# MDAS_Controller_V1.net
KiCad netlist of a schematic drawn in EAGLE
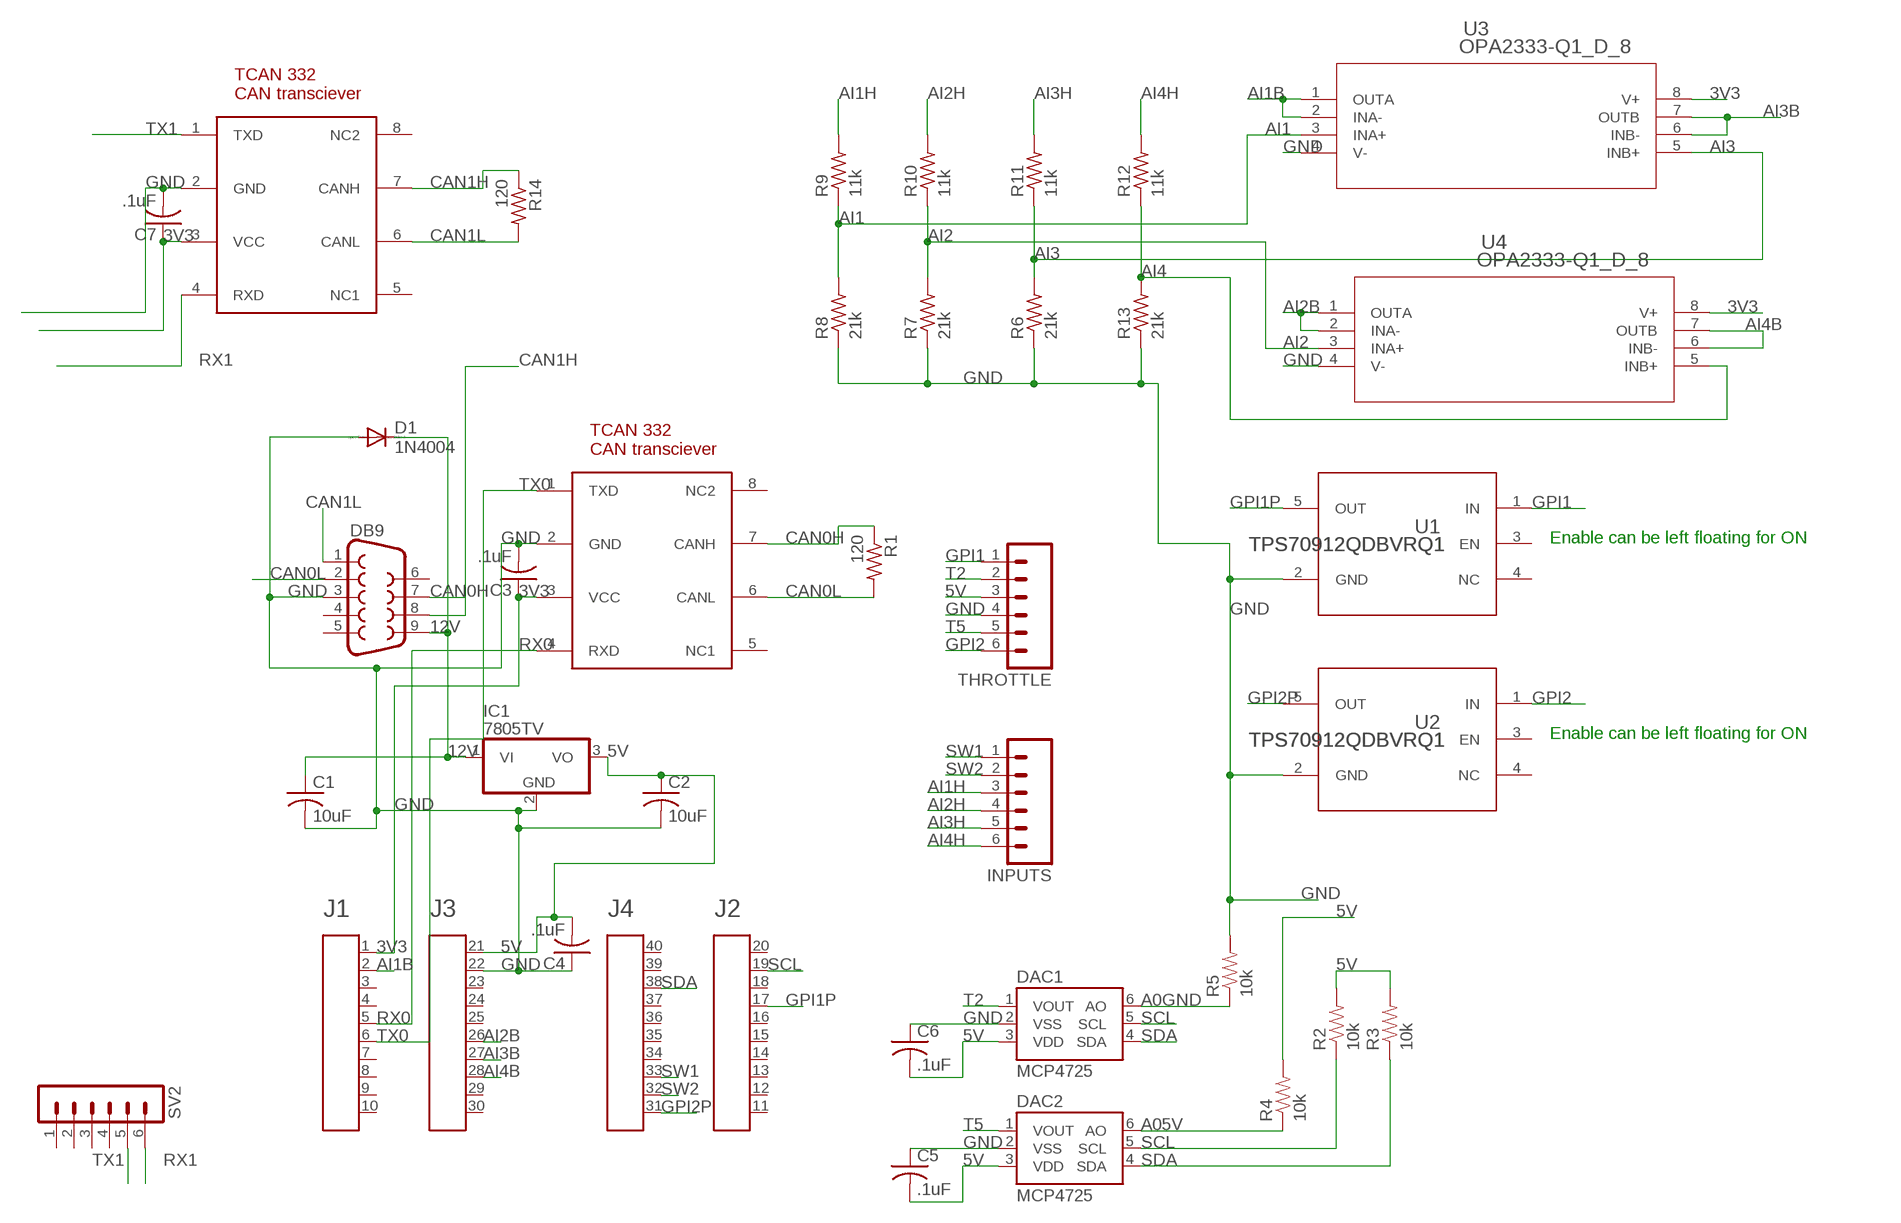
[diagram p0: schematic, sheet 1]

(export (version "E")
  (design (tool "Eeschema 10.0.6"))
  (components
    (comp (ref "A1")
      (value "HEADER4X10-BOOSTERPACK")
      (footprint "eagle-import:4X10-BOOSTERPACK")
      (libsource (lib "eagle-import") (part "HEADER4X10-BOOSTERPACK"))
    )
    (comp (ref "C1")
      (value "10uF")
      (footprint "eagle-import:C1206K")
      (libsource (lib "eagle-import") (part "C-USC1206K"))
    )
    (comp (ref "C2")
      (value "10uF")
      (footprint "eagle-import:C1206K")
      (libsource (lib "eagle-import") (part "C-USC1206K"))
    )
    (comp (ref "C3")
      (value ".1uF")
      (footprint "eagle-import:C0603")
      (libsource (lib "eagle-import") (part "adafruit_420_C-USC0603"))
    )
    (comp (ref "C4")
      (value ".1uF")
      (footprint "eagle-import:C0603")
      (libsource (lib "eagle-import") (part "adafruit_420_C-USC0603"))
    )
    (comp (ref "C5")
      (value ".1uF")
      (footprint "eagle-import:C0603")
      (libsource (lib "eagle-import") (part "adafruit_420_C-USC0603"))
    )
    (comp (ref "C6")
      (value ".1uF")
      (footprint "eagle-import:C0603")
      (libsource (lib "eagle-import") (part "adafruit_420_C-USC0603"))
    )
    (comp (ref "C7")
      (value ".1uF")
      (footprint "eagle-import:C0603")
      (libsource (lib "eagle-import") (part "adafruit_420_C-USC0603"))
    )
    (comp (ref "CAN_TRANSCIEVER")
      (value "TCAN332")
      (footprint "eagle-import:SOIC127P600X172-8N")
      (libsource (lib "eagle-import") (part "TCAN332"))
    )
    (comp (ref "CAN_TRANSCIEVER1")
      (value "TCAN332")
      (footprint "eagle-import:SOIC127P600X172-8N")
      (libsource (lib "eagle-import") (part "TCAN332"))
    )
    (comp (ref "D1")
      (value "1N4004")
      (footprint "eagle-import:DO41-10")
      (libsource (lib "eagle-import") (part "1N4004"))
    )
    (comp (ref "DAC1")
      (value "MCP4725")
      (footprint "eagle-import:SOT23-6")
      (libsource (lib "eagle-import") (part "MCP4725SOT-23"))
    )
    (comp (ref "DAC2")
      (value "MCP4725")
      (footprint "eagle-import:SOT23-6")
      (libsource (lib "eagle-import") (part "MCP4725SOT-23"))
    )
    (comp (ref "DB9")
      (value "DB9FEMALE")
      (footprint "eagle-import:DB9")
      (libsource (lib "eagle-import") (part "DB9FEMALE"))
    )
    (comp (ref "IC1")
      (value "7805TV")
      (footprint "eagle-import:TO220V")
      (libsource (lib "eagle-import") (part "78TV05"))
    )
    (comp (ref "INPUTS")
      (value "M06SMD-1MM")
      (footprint "eagle-import:1X06-1MM")
      (libsource (lib "eagle-import") (part "M06SMD-1MM"))
    )
    (comp (ref "R1")
      (value "120")
      (footprint "eagle-import:0207_10")
      (libsource (lib "eagle-import") (part "adafruit_420_R-US_0207/10"))
    )
    (comp (ref "R2")
      (value "10k")
      (footprint "eagle-import:0603-RES")
      (libsource (lib "eagle-import") (part "RESISTOR0603-RES"))
    )
    (comp (ref "R3")
      (value "10k")
      (footprint "eagle-import:0603-RES")
      (libsource (lib "eagle-import") (part "RESISTOR0603-RES"))
    )
    (comp (ref "R4")
      (value "10k")
      (footprint "eagle-import:0603-RES")
      (libsource (lib "eagle-import") (part "RESISTOR0603-RES"))
    )
    (comp (ref "R5")
      (value "10k")
      (footprint "eagle-import:0603-RES")
      (libsource (lib "eagle-import") (part "RESISTOR0603-RES"))
    )
    (comp (ref "R6")
      (value "21k")
      (footprint "eagle-import:R0603")
      (libsource (lib "eagle-import") (part "R-US_R0603"))
    )
    (comp (ref "R7")
      (value "21k")
      (footprint "eagle-import:R0603")
      (libsource (lib "eagle-import") (part "R-US_R0603"))
    )
    (comp (ref "R8")
      (value "21k")
      (footprint "eagle-import:R0603")
      (libsource (lib "eagle-import") (part "R-US_R0603"))
    )
    (comp (ref "R9")
      (value "11k")
      (footprint "eagle-import:R0603")
      (libsource (lib "eagle-import") (part "R-US_R0603"))
    )
    (comp (ref "R10")
      (value "11k")
      (footprint "eagle-import:R0603")
      (libsource (lib "eagle-import") (part "R-US_R0603"))
    )
    (comp (ref "R11")
      (value "11k")
      (footprint "eagle-import:R0603")
      (libsource (lib "eagle-import") (part "R-US_R0603"))
    )
    (comp (ref "R12")
      (value "11k")
      (footprint "eagle-import:R0603")
      (libsource (lib "eagle-import") (part "R-US_R0603"))
    )
    (comp (ref "R13")
      (value "21k")
      (footprint "eagle-import:R0603")
      (libsource (lib "eagle-import") (part "R-US_R0603"))
    )
    (comp (ref "R14")
      (value "120")
      (footprint "eagle-import:0207_10")
      (libsource (lib "eagle-import") (part "adafruit_420_R-US_0207/10"))
    )
    (comp (ref "SV2")
      (value "MA06-1")
      (footprint "eagle-import:MA06-1")
      (libsource (lib "eagle-import") (part "MA06-1"))
    )
    (comp (ref "THROTTLE")
      (value "M06SMD-1MM")
      (footprint "eagle-import:1X06-1MM")
      (libsource (lib "eagle-import") (part "M06SMD-1MM"))
    )
    (comp (ref "U1")
      (value "TPS70912QDBVRQ1")
      (footprint "eagle-import:DBV0005A_N")
      (libsource (lib "eagle-import") (part "TPS70912QDBVRQ1"))
    )
    (comp (ref "U2")
      (value "TPS70912QDBVRQ1")
      (footprint "eagle-import:DBV0005A_N")
      (libsource (lib "eagle-import") (part "TPS70912QDBVRQ1"))
    )
    (comp (ref "U3")
      (value "OPA2333-Q1_D_8")
      (footprint "eagle-import:D8")
      (fields (field (name "MANUFACTURER_PART_NUMBER") "opa2333q1_d_8"))
      (libsource (lib "eagle-import") (part "OPA2333-Q1_D_8"))
    )
    (comp (ref "U4")
      (value "OPA2333-Q1_D_8")
      (footprint "eagle-import:D8")
      (fields (field (name "MANUFACTURER_PART_NUMBER") "opa2333q1_d_8"))
      (libsource (lib "eagle-import") (part "OPA2333-Q1_D_8"))
    )
  )
  (nets
    (net (code "1") (name "/3V3") (class "Default")
      (node (ref "A1") (pin "1") (pinfunction "P$1_1") (pintype "bidirectional"))
      (node (ref "C3") (pin "1") (pinfunction "1_1") (pintype "passive"))
      (node (ref "C7") (pin "1") (pinfunction "1_1") (pintype "passive"))
      (node (ref "CAN_TRANSCIEVER") (pin "3") (pinfunction "VCC_3") (pintype "bidirectional"))
      (node (ref "CAN_TRANSCIEVER1") (pin "3") (pinfunction "VCC_3") (pintype "bidirectional"))
      (node (ref "U3") (pin "8") (pinfunction "V+_8") (pintype "power_in"))
      (node (ref "U4") (pin "8") (pinfunction "V+_8") (pintype "power_in"))
    )
    (net (code "2") (name "/5V") (class "Default")
      (node (ref "A1") (pin "21") (pinfunction "P$21_21") (pintype "bidirectional"))
      (node (ref "C2") (pin "1") (pinfunction "1_1") (pintype "passive"))
      (node (ref "C4") (pin "2") (pinfunction "2_2") (pintype "passive"))
      (node (ref "C5") (pin "2") (pinfunction "2_2") (pintype "passive"))
      (node (ref "C6") (pin "2") (pinfunction "2_2") (pintype "passive"))
      (node (ref "DAC1") (pin "3") (pinfunction "VDD_3") (pintype "bidirectional"))
      (node (ref "DAC2") (pin "3") (pinfunction "VDD_3") (pintype "bidirectional"))
      (node (ref "IC1") (pin "3") (pinfunction "VO_3") (pintype "passive"))
      (node (ref "R2") (pin "2") (pinfunction "2_2") (pintype "passive"))
      (node (ref "R3") (pin "2") (pinfunction "2_2") (pintype "passive"))
      (node (ref "R4") (pin "2") (pinfunction "2_2") (pintype "passive"))
      (node (ref "THROTTLE") (pin "3") (pinfunction "3_3") (pintype "passive"))
    )
    (net (code "3") (name "/12V") (class "Default")
      (node (ref "C1") (pin "1") (pinfunction "1_1") (pintype "passive"))
      (node (ref "D1") (pin "C") (pinfunction "C_C") (pintype "passive"))
      (node (ref "DB9") (pin "9") (pinfunction "9_9") (pintype "passive"))
      (node (ref "IC1") (pin "1") (pinfunction "VI_1") (pintype "input"))
    )
    (net (code "4") (name "/A0GND") (class "Default")
      (node (ref "DAC1") (pin "6") (pinfunction "AO_6") (pintype "bidirectional"))
      (node (ref "R5") (pin "1") (pinfunction "1_1") (pintype "passive"))
    )
    (net (code "5") (name "/A05V") (class "Default")
      (node (ref "DAC2") (pin "6") (pinfunction "AO_6") (pintype "bidirectional"))
      (node (ref "R4") (pin "1") (pinfunction "1_1") (pintype "passive"))
    )
    (net (code "6") (name "/AI1") (class "Default")
      (node (ref "R8") (pin "2") (pinfunction "2_2") (pintype "passive"))
      (node (ref "R9") (pin "1") (pinfunction "1_1") (pintype "passive"))
      (node (ref "U3") (pin "3") (pinfunction "INA+_3") (pintype "input"))
    )
    (net (code "7") (name "/AI1B") (class "Default")
      (node (ref "A1") (pin "2") (pinfunction "P$2_2") (pintype "bidirectional"))
      (node (ref "U3") (pin "1") (pinfunction "OUTA_1") (pintype "output"))
      (node (ref "U3") (pin "2") (pinfunction "INA-_2") (pintype "input"))
    )
    (net (code "8") (name "/AI1H") (class "Default")
      (node (ref "INPUTS") (pin "3") (pinfunction "3_3") (pintype "passive"))
      (node (ref "R9") (pin "2") (pinfunction "2_2") (pintype "passive"))
    )
    (net (code "9") (name "/AI2") (class "Default")
      (node (ref "R10") (pin "1") (pinfunction "1_1") (pintype "passive"))
      (node (ref "R7") (pin "2") (pinfunction "2_2") (pintype "passive"))
      (node (ref "U4") (pin "3") (pinfunction "INA+_3") (pintype "input"))
    )
    (net (code "10") (name "/AI2B") (class "Default")
      (node (ref "A1") (pin "26") (pinfunction "P$26_26") (pintype "bidirectional"))
      (node (ref "U4") (pin "1") (pinfunction "OUTA_1") (pintype "output"))
      (node (ref "U4") (pin "2") (pinfunction "INA-_2") (pintype "input"))
    )
    (net (code "11") (name "/AI2H") (class "Default")
      (node (ref "INPUTS") (pin "4") (pinfunction "4_4") (pintype "passive"))
      (node (ref "R10") (pin "2") (pinfunction "2_2") (pintype "passive"))
    )
    (net (code "12") (name "/AI3") (class "Default")
      (node (ref "R11") (pin "1") (pinfunction "1_1") (pintype "passive"))
      (node (ref "R6") (pin "2") (pinfunction "2_2") (pintype "passive"))
      (node (ref "U3") (pin "5") (pinfunction "INB+_5") (pintype "input"))
    )
    (net (code "13") (name "/AI3B") (class "Default")
      (node (ref "A1") (pin "27") (pinfunction "P$27_27") (pintype "bidirectional"))
      (node (ref "U3") (pin "6") (pinfunction "INB-_6") (pintype "input"))
      (node (ref "U3") (pin "7") (pinfunction "OUTB_7") (pintype "output"))
    )
    (net (code "14") (name "/AI3H") (class "Default")
      (node (ref "INPUTS") (pin "5") (pinfunction "5_5") (pintype "passive"))
      (node (ref "R11") (pin "2") (pinfunction "2_2") (pintype "passive"))
    )
    (net (code "15") (name "/AI4") (class "Default")
      (node (ref "R12") (pin "1") (pinfunction "1_1") (pintype "passive"))
      (node (ref "R13") (pin "2") (pinfunction "2_2") (pintype "passive"))
      (node (ref "U4") (pin "5") (pinfunction "INB+_5") (pintype "input"))
    )
    (net (code "16") (name "/AI4B") (class "Default")
      (node (ref "A1") (pin "28") (pinfunction "P$28_28") (pintype "bidirectional"))
      (node (ref "U4") (pin "6") (pinfunction "INB-_6") (pintype "input"))
      (node (ref "U4") (pin "7") (pinfunction "OUTB_7") (pintype "output"))
    )
    (net (code "17") (name "/AI4H") (class "Default")
      (node (ref "INPUTS") (pin "6") (pinfunction "6_6") (pintype "passive"))
      (node (ref "R12") (pin "2") (pinfunction "2_2") (pintype "passive"))
    )
    (net (code "18") (name "/CAN0H") (class "Default")
      (node (ref "CAN_TRANSCIEVER") (pin "7") (pinfunction "CANH_7") (pintype "bidirectional"))
      (node (ref "DB9") (pin "7") (pinfunction "7_7") (pintype "passive"))
      (node (ref "R1") (pin "1") (pinfunction "1_1") (pintype "passive"))
    )
    (net (code "19") (name "/CAN0L") (class "Default")
      (node (ref "CAN_TRANSCIEVER") (pin "6") (pinfunction "CANL_6") (pintype "bidirectional"))
      (node (ref "DB9") (pin "2") (pinfunction "2_2") (pintype "passive"))
      (node (ref "R1") (pin "2") (pinfunction "2_2") (pintype "passive"))
    )
    (net (code "20") (name "/CAN1H") (class "Default")
      (node (ref "CAN_TRANSCIEVER1") (pin "7") (pinfunction "CANH_7") (pintype "bidirectional"))
      (node (ref "DB9") (pin "8") (pinfunction "8_8") (pintype "passive"))
      (node (ref "R14") (pin "1") (pinfunction "1_1") (pintype "passive"))
    )
    (net (code "21") (name "/CAN1L") (class "Default")
      (node (ref "CAN_TRANSCIEVER1") (pin "6") (pinfunction "CANL_6") (pintype "bidirectional"))
      (node (ref "DB9") (pin "1") (pinfunction "1_1") (pintype "passive"))
      (node (ref "R14") (pin "2") (pinfunction "2_2") (pintype "passive"))
    )
    (net (code "22") (name "/GND") (class "Default")
      (node (ref "A1") (pin "22") (pinfunction "P$22_22") (pintype "bidirectional"))
      (node (ref "C1") (pin "2") (pinfunction "2_2") (pintype "passive"))
      (node (ref "C2") (pin "2") (pinfunction "2_2") (pintype "passive"))
      (node (ref "C3") (pin "2") (pinfunction "2_2") (pintype "passive"))
      (node (ref "C4") (pin "1") (pinfunction "1_1") (pintype "passive"))
      (node (ref "C5") (pin "1") (pinfunction "1_1") (pintype "passive"))
      (node (ref "C6") (pin "1") (pinfunction "1_1") (pintype "passive"))
      (node (ref "C7") (pin "2") (pinfunction "2_2") (pintype "passive"))
      (node (ref "CAN_TRANSCIEVER") (pin "2") (pinfunction "GND_2") (pintype "bidirectional"))
      (node (ref "CAN_TRANSCIEVER1") (pin "2") (pinfunction "GND_2") (pintype "bidirectional"))
      (node (ref "D1") (pin "A") (pinfunction "A_A") (pintype "passive"))
      (node (ref "DAC1") (pin "2") (pinfunction "VSS_2") (pintype "bidirectional"))
      (node (ref "DAC2") (pin "2") (pinfunction "VSS_2") (pintype "bidirectional"))
      (node (ref "DB9") (pin "3") (pinfunction "3_3") (pintype "passive"))
      (node (ref "IC1") (pin "2") (pinfunction "GND_2") (pintype "passive"))
      (node (ref "R13") (pin "1") (pinfunction "1_1") (pintype "passive"))
      (node (ref "R5") (pin "2") (pinfunction "2_2") (pintype "passive"))
      (node (ref "R6") (pin "1") (pinfunction "1_1") (pintype "passive"))
      (node (ref "R7") (pin "1") (pinfunction "1_1") (pintype "passive"))
      (node (ref "R8") (pin "1") (pinfunction "1_1") (pintype "passive"))
      (node (ref "THROTTLE") (pin "4") (pinfunction "4_4") (pintype "passive"))
      (node (ref "U1") (pin "2") (pinfunction "GND_2") (pintype "power_in"))
      (node (ref "U2") (pin "2") (pinfunction "GND_2") (pintype "power_in"))
      (node (ref "U3") (pin "4") (pinfunction "V-_4") (pintype "power_in"))
      (node (ref "U4") (pin "4") (pinfunction "V-_4") (pintype "power_in"))
    )
    (net (code "23") (name "/GPI1") (class "Default")
      (node (ref "THROTTLE") (pin "1") (pinfunction "1_1") (pintype "passive"))
      (node (ref "U1") (pin "1") (pinfunction "IN_1") (pintype "power_in"))
    )
    (net (code "24") (name "/GPI1P") (class "Default")
      (node (ref "A1") (pin "17") (pinfunction "P$17_17") (pintype "bidirectional"))
      (node (ref "U1") (pin "5") (pinfunction "OUT_5") (pintype "power_in"))
    )
    (net (code "25") (name "/GPI2") (class "Default")
      (node (ref "THROTTLE") (pin "6") (pinfunction "6_6") (pintype "passive"))
      (node (ref "U2") (pin "1") (pinfunction "IN_1") (pintype "power_in"))
    )
    (net (code "26") (name "/GPI2P") (class "Default")
      (node (ref "A1") (pin "31") (pinfunction "P$31_31") (pintype "bidirectional"))
      (node (ref "U2") (pin "5") (pinfunction "OUT_5") (pintype "power_in"))
    )
    (net (code "27") (name "/RX0") (class "Default")
      (node (ref "A1") (pin "5") (pinfunction "P$5_5") (pintype "bidirectional"))
      (node (ref "CAN_TRANSCIEVER") (pin "4") (pinfunction "RXD_4") (pintype "bidirectional"))
    )
    (net (code "28") (name "/RX1") (class "Default")
      (node (ref "CAN_TRANSCIEVER1") (pin "4") (pinfunction "RXD_4") (pintype "bidirectional"))
      (node (ref "SV2") (pin "6") (pinfunction "6_6") (pintype "passive"))
    )
    (net (code "29") (name "/SCL") (class "Default")
      (node (ref "A1") (pin "19") (pinfunction "P$19_19") (pintype "bidirectional"))
      (node (ref "DAC1") (pin "5") (pinfunction "SCL_5") (pintype "bidirectional"))
      (node (ref "DAC2") (pin "5") (pinfunction "SCL_5") (pintype "bidirectional"))
      (node (ref "R2") (pin "1") (pinfunction "1_1") (pintype "passive"))
    )
    (net (code "30") (name "/SDA") (class "Default")
      (node (ref "A1") (pin "38") (pinfunction "P$38_38") (pintype "bidirectional"))
      (node (ref "DAC1") (pin "4") (pinfunction "SDA_4") (pintype "bidirectional"))
      (node (ref "DAC2") (pin "4") (pinfunction "SDA_4") (pintype "bidirectional"))
      (node (ref "R3") (pin "1") (pinfunction "1_1") (pintype "passive"))
    )
    (net (code "31") (name "/SW1") (class "Default")
      (node (ref "A1") (pin "33") (pinfunction "P$33_33") (pintype "bidirectional"))
      (node (ref "INPUTS") (pin "1") (pinfunction "1_1") (pintype "passive"))
    )
    (net (code "32") (name "/SW2") (class "Default")
      (node (ref "A1") (pin "32") (pinfunction "P$32_32") (pintype "bidirectional"))
      (node (ref "INPUTS") (pin "2") (pinfunction "2_2") (pintype "passive"))
    )
    (net (code "33") (name "/T2") (class "Default")
      (node (ref "DAC1") (pin "1") (pinfunction "VOUT_1") (pintype "bidirectional"))
      (node (ref "THROTTLE") (pin "2") (pinfunction "2_2") (pintype "passive"))
    )
    (net (code "34") (name "/T5") (class "Default")
      (node (ref "DAC2") (pin "1") (pinfunction "VOUT_1") (pintype "bidirectional"))
      (node (ref "THROTTLE") (pin "5") (pinfunction "5_5") (pintype "passive"))
    )
    (net (code "35") (name "/TX0") (class "Default")
      (node (ref "A1") (pin "6") (pinfunction "P$6_6") (pintype "bidirectional"))
      (node (ref "CAN_TRANSCIEVER") (pin "1") (pinfunction "TXD_1") (pintype "bidirectional"))
    )
    (net (code "36") (name "/TX1") (class "Default")
      (node (ref "CAN_TRANSCIEVER1") (pin "1") (pinfunction "TXD_1") (pintype "bidirectional"))
      (node (ref "SV2") (pin "5") (pinfunction "5_5") (pintype "passive"))
    )
    (net (code "37") (name "unconnected-(A1-P$3-Pad3)") (class "Default")
      (node (ref "A1") (pin "3") (pinfunction "P$3_3") (pintype "bidirectional"))
    )
    (net (code "38") (name "unconnected-(A1-P$4-Pad4)") (class "Default")
      (node (ref "A1") (pin "4") (pinfunction "P$4_4") (pintype "bidirectional"))
    )
    (net (code "39") (name "unconnected-(A1-P$7-Pad7)") (class "Default")
      (node (ref "A1") (pin "7") (pinfunction "P$7_7") (pintype "bidirectional"))
    )
    (net (code "40") (name "unconnected-(A1-P$8-Pad8)") (class "Default")
      (node (ref "A1") (pin "8") (pinfunction "P$8_8") (pintype "bidirectional"))
    )
    (net (code "41") (name "unconnected-(A1-P$9-Pad9)") (class "Default")
      (node (ref "A1") (pin "9") (pinfunction "P$9_9") (pintype "bidirectional"))
    )
    (net (code "42") (name "unconnected-(A1-P$10-Pad10)") (class "Default")
      (node (ref "A1") (pin "10") (pinfunction "P$10_10") (pintype "bidirectional"))
    )
    (net (code "43") (name "unconnected-(A1-P$11-Pad11)") (class "Default")
      (node (ref "A1") (pin "11") (pinfunction "P$11_11") (pintype "bidirectional"))
    )
    (net (code "44") (name "unconnected-(A1-P$12-Pad12)") (class "Default")
      (node (ref "A1") (pin "12") (pinfunction "P$12_12") (pintype "bidirectional"))
    )
    (net (code "45") (name "unconnected-(A1-P$13-Pad13)") (class "Default")
      (node (ref "A1") (pin "13") (pinfunction "P$13_13") (pintype "bidirectional"))
    )
    (net (code "46") (name "unconnected-(A1-P$14-Pad14)") (class "Default")
      (node (ref "A1") (pin "14") (pinfunction "P$14_14") (pintype "bidirectional"))
    )
    (net (code "47") (name "unconnected-(A1-P$15-Pad15)") (class "Default")
      (node (ref "A1") (pin "15") (pinfunction "P$15_15") (pintype "bidirectional"))
    )
    (net (code "48") (name "unconnected-(A1-P$16-Pad16)") (class "Default")
      (node (ref "A1") (pin "16") (pinfunction "P$16_16") (pintype "bidirectional"))
    )
    (net (code "49") (name "unconnected-(A1-P$18-Pad18)") (class "Default")
      (node (ref "A1") (pin "18") (pinfunction "P$18_18") (pintype "bidirectional"))
    )
    (net (code "50") (name "unconnected-(A1-P$20-Pad20)") (class "Default")
      (node (ref "A1") (pin "20") (pinfunction "P$20_20") (pintype "bidirectional"))
    )
    (net (code "51") (name "unconnected-(A1-P$23-Pad23)") (class "Default")
      (node (ref "A1") (pin "23") (pinfunction "P$23_23") (pintype "bidirectional"))
    )
    (net (code "52") (name "unconnected-(A1-P$24-Pad24)") (class "Default")
      (node (ref "A1") (pin "24") (pinfunction "P$24_24") (pintype "bidirectional"))
    )
    (net (code "53") (name "unconnected-(A1-P$25-Pad25)") (class "Default")
      (node (ref "A1") (pin "25") (pinfunction "P$25_25") (pintype "bidirectional"))
    )
    (net (code "54") (name "unconnected-(A1-P$29-Pad29)") (class "Default")
      (node (ref "A1") (pin "29") (pinfunction "P$29_29") (pintype "bidirectional"))
    )
    (net (code "55") (name "unconnected-(A1-P$30-Pad30)") (class "Default")
      (node (ref "A1") (pin "30") (pinfunction "P$30_30") (pintype "bidirectional"))
    )
    (net (code "56") (name "unconnected-(A1-P$34-Pad34)") (class "Default")
      (node (ref "A1") (pin "34") (pinfunction "P$34_34") (pintype "bidirectional"))
    )
    (net (code "57") (name "unconnected-(A1-P$35-Pad35)") (class "Default")
      (node (ref "A1") (pin "35") (pinfunction "P$35_35") (pintype "bidirectional"))
    )
    (net (code "58") (name "unconnected-(A1-P$36-Pad36)") (class "Default")
      (node (ref "A1") (pin "36") (pinfunction "P$36_36") (pintype "bidirectional"))
    )
    (net (code "59") (name "unconnected-(A1-P$37-Pad37)") (class "Default")
      (node (ref "A1") (pin "37") (pinfunction "P$37_37") (pintype "bidirectional"))
    )
    (net (code "60") (name "unconnected-(A1-P$39-Pad39)") (class "Default")
      (node (ref "A1") (pin "39") (pinfunction "P$39_39") (pintype "bidirectional"))
    )
    (net (code "61") (name "unconnected-(A1-P$40-Pad40)") (class "Default")
      (node (ref "A1") (pin "40") (pinfunction "P$40_40") (pintype "bidirectional"))
    )
    (net (code "62") (name "unconnected-(CAN_TRANSCIEVER-NC1-Pad5)") (class "Default")
      (node (ref "CAN_TRANSCIEVER") (pin "5") (pinfunction "NC1_5") (pintype "bidirectional"))
    )
    (net (code "63") (name "unconnected-(CAN_TRANSCIEVER-NC2-Pad8)") (class "Default")
      (node (ref "CAN_TRANSCIEVER") (pin "8") (pinfunction "NC2_8") (pintype "bidirectional"))
    )
    (net (code "64") (name "unconnected-(CAN_TRANSCIEVER1-NC1-Pad5)") (class "Default")
      (node (ref "CAN_TRANSCIEVER1") (pin "5") (pinfunction "NC1_5") (pintype "bidirectional"))
    )
    (net (code "65") (name "unconnected-(CAN_TRANSCIEVER1-NC2-Pad8)") (class "Default")
      (node (ref "CAN_TRANSCIEVER1") (pin "8") (pinfunction "NC2_8") (pintype "bidirectional"))
    )
    (net (code "66") (name "unconnected-(DB9-Pad4)") (class "Default")
      (node (ref "DB9") (pin "4") (pinfunction "4_4") (pintype "passive"))
    )
    (net (code "67") (name "unconnected-(DB9-Pad5)") (class "Default")
      (node (ref "DB9") (pin "5") (pinfunction "5_5") (pintype "passive"))
    )
    (net (code "68") (name "unconnected-(DB9-Pad6)") (class "Default")
      (node (ref "DB9") (pin "6") (pinfunction "6_6") (pintype "passive"))
    )
    (net (code "69") (name "unconnected-(SV2-Pad1)") (class "Default")
      (node (ref "SV2") (pin "1") (pinfunction "1_1") (pintype "passive"))
    )
    (net (code "70") (name "unconnected-(SV2-Pad2)") (class "Default")
      (node (ref "SV2") (pin "2") (pinfunction "2_2") (pintype "passive"))
    )
    (net (code "71") (name "unconnected-(SV2-Pad3)") (class "Default")
      (node (ref "SV2") (pin "3") (pinfunction "3_3") (pintype "passive"))
    )
    (net (code "72") (name "unconnected-(SV2-Pad4)") (class "Default")
      (node (ref "SV2") (pin "4") (pinfunction "4_4") (pintype "passive"))
    )
    (net (code "73") (name "unconnected-(U1-EN-Pad3)") (class "Default")
      (node (ref "U1") (pin "3") (pinfunction "EN_3") (pintype "input"))
    )
    (net (code "74") (name "unconnected-(U1-NC-Pad4)") (class "Default")
      (node (ref "U1") (pin "4") (pinfunction "NC_4") (pintype "passive"))
    )
    (net (code "75") (name "unconnected-(U2-EN-Pad3)") (class "Default")
      (node (ref "U2") (pin "3") (pinfunction "EN_3") (pintype "input"))
    )
    (net (code "76") (name "unconnected-(U2-NC-Pad4)") (class "Default")
      (node (ref "U2") (pin "4") (pinfunction "NC_4") (pintype "passive"))
    )
  )
)
